# gps-power.net
KiCad netlist of a schematic drawn in EAGLE
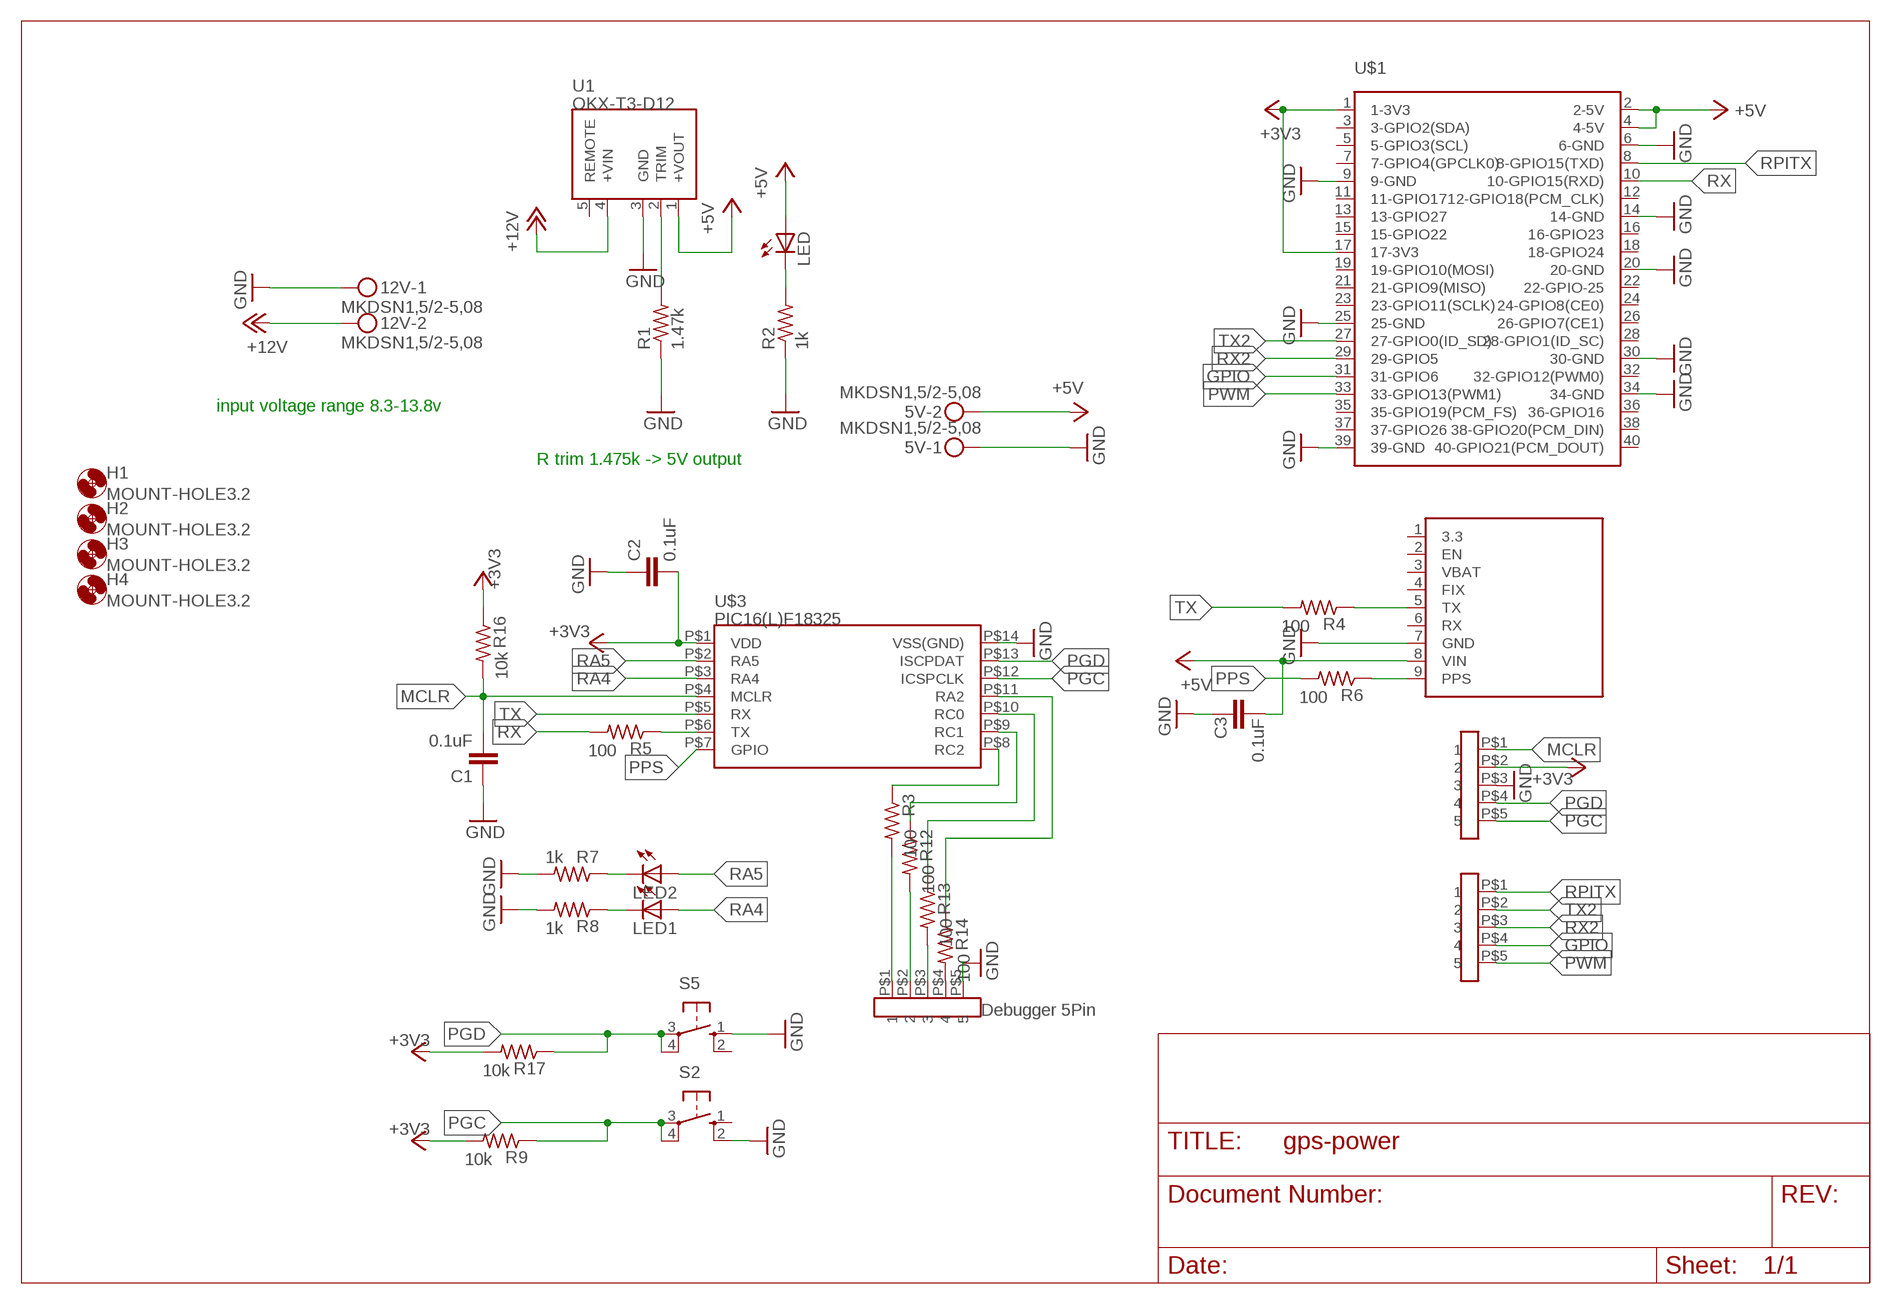
[diagram p0: schematic, sheet 1]

(export (version "E")
  (design (tool "Eeschema 10.0.6"))
  (components
    (comp (ref "5V")
      (value "MKDSN1,5/2-5,08")
      (footprint "eagle-import:MKDSN1,5_2-5,08")
      (libsource (lib "eagle-import") (part "MKDSN1,5/2-5,08"))
    )
    (comp (ref "8,9,10,11,GND")
      (value "PIN-5")
      (footprint "eagle-import:PIN-5")
      (libsource (lib "eagle-import") (part "PIN-5"))
    )
    (comp (ref "12V")
      (value "MKDSN1,5/2-5,08")
      (footprint "eagle-import:MKDSN1,5_2-5,08")
      (libsource (lib "eagle-import") (part "MKDSN1,5/2-5,08"))
    )
    (comp (ref "C1")
      (value "0.1uF")
      (footprint "eagle-import:0603")
      (libsource (lib "eagle-import") (part "0.1UF-0603-25V-5%"))
    )
    (comp (ref "C2")
      (value "0.1uF")
      (footprint "eagle-import:0603")
      (libsource (lib "eagle-import") (part "0.1UF-0603-25V-5%"))
    )
    (comp (ref "C3")
      (value "0.1uF")
      (footprint "eagle-import:0603")
      (libsource (lib "eagle-import") (part "0.1UF-0603-25V-5%"))
    )
    (comp (ref "GND")
      (value "PIN-5")
      (footprint "eagle-import:PIN-5")
      (libsource (lib "eagle-import") (part "PIN-5"))
    )
    (comp (ref "H1")
      (value "MOUNT-HOLE3.2")
      (footprint "eagle-import:3,2")
      (libsource (lib "eagle-import") (part "MOUNT-HOLE3.2"))
    )
    (comp (ref "H2")
      (value "MOUNT-HOLE3.2")
      (footprint "eagle-import:3,2")
      (libsource (lib "eagle-import") (part "MOUNT-HOLE3.2"))
    )
    (comp (ref "H3")
      (value "MOUNT-HOLE3.2")
      (footprint "eagle-import:3,2")
      (libsource (lib "eagle-import") (part "MOUNT-HOLE3.2"))
    )
    (comp (ref "H4")
      (value "MOUNT-HOLE3.2")
      (footprint "eagle-import:3,2")
      (libsource (lib "eagle-import") (part "MOUNT-HOLE3.2"))
    )
    (comp (ref "LED")
      (value "LEDCHIPLED_0603")
      (footprint "eagle-import:CHIPLED_0603")
      (libsource (lib "eagle-import") (part "LEDCHIPLED_0603"))
    )
    (comp (ref "LED1")
      (value "LEDCHIPLED_0603")
      (footprint "eagle-import:CHIPLED_0603")
      (libsource (lib "eagle-import") (part "LEDCHIPLED_0603"))
    )
    (comp (ref "LED2")
      (value "LEDCHIPLED_0603")
      (footprint "eagle-import:CHIPLED_0603")
      (libsource (lib "eagle-import") (part "LEDCHIPLED_0603"))
    )
    (comp (ref "MPLAB")
      (value "PIN-5")
      (footprint "eagle-import:PIN-5")
      (libsource (lib "eagle-import") (part "PIN-5"))
    )
    (comp (ref "R1")
      (value "1.47k")
      (footprint "eagle-import:R0603")
      (libsource (lib "eagle-import") (part "R-US_R0603"))
    )
    (comp (ref "R2")
      (value "1k")
      (footprint "eagle-import:R0603")
      (libsource (lib "eagle-import") (part "R-US_R0603"))
    )
    (comp (ref "R3")
      (value "100")
      (footprint "eagle-import:R0603")
      (libsource (lib "eagle-import") (part "R-US_R0603"))
    )
    (comp (ref "R4")
      (value "100")
      (footprint "eagle-import:R0603")
      (libsource (lib "eagle-import") (part "R-US_R0603"))
    )
    (comp (ref "R5")
      (value "100")
      (footprint "eagle-import:R0603")
      (libsource (lib "eagle-import") (part "R-US_R0603"))
    )
    (comp (ref "R6")
      (value "100")
      (footprint "eagle-import:R0603")
      (libsource (lib "eagle-import") (part "R-US_R0603"))
    )
    (comp (ref "R7")
      (value "1k")
      (footprint "eagle-import:R0603")
      (libsource (lib "eagle-import") (part "R-US_R0603"))
    )
    (comp (ref "R8")
      (value "1k")
      (footprint "eagle-import:R0603")
      (libsource (lib "eagle-import") (part "R-US_R0603"))
    )
    (comp (ref "R9")
      (value "10k")
      (footprint "eagle-import:R0603")
      (libsource (lib "eagle-import") (part "R-US_R0603"))
    )
    (comp (ref "R12")
      (value "100")
      (footprint "eagle-import:R0603")
      (libsource (lib "eagle-import") (part "R-US_R0603"))
    )
    (comp (ref "R13")
      (value "100")
      (footprint "eagle-import:R0603")
      (libsource (lib "eagle-import") (part "R-US_R0603"))
    )
    (comp (ref "R14")
      (value "100")
      (footprint "eagle-import:R0603")
      (libsource (lib "eagle-import") (part "R-US_R0603"))
    )
    (comp (ref "R16")
      (value "10k")
      (footprint "eagle-import:R0603")
      (libsource (lib "eagle-import") (part "R-US_R0603"))
    )
    (comp (ref "R17")
      (value "10k")
      (footprint "eagle-import:R0603")
      (libsource (lib "eagle-import") (part "R-US_R0603"))
    )
    (comp (ref "S2")
      (value "10-XX")
      (footprint "eagle-import:B3F-10XX")
      (fields (field (name "MPN") "B3F-1000"))
      (libsource (lib "eagle-import") (part "10-XX"))
    )
    (comp (ref "S5")
      (value "10-XX")
      (footprint "eagle-import:B3F-10XX")
      (fields (field (name "MPN") "B3F-1000"))
      (libsource (lib "eagle-import") (part "10-XX"))
    )
    (comp (ref "U$1")
      (value "GPIO-HD-2X20")
      (footprint "eagle-import:GPIO-HD-2X20")
      (libsource (lib "eagle-import") (part "GPIO-HD-2X20"))
    )
    (comp (ref "U$2")
      (value "ADA-GPS")
      (footprint "eagle-import:ADA-GPS")
      (libsource (lib "eagle-import") (part "ADA-GPS"))
    )
    (comp (ref "U$3")
      (value "PIC16(L)F18325")
      (footprint "eagle-import:DIP-S-14")
      (libsource (lib "eagle-import") (part "PIC16(L)F18325"))
    )
    (comp (ref "U1")
      (value "OKX-T3-D12")
      (footprint "eagle-import:OKX-T3-D12")
      (libsource (lib "eagle-import") (part "OKX-T3-D12"))
    )
  )
  (nets
    (net (code "1") (name "+3V3") (class "Default")
      (node (ref "C2") (pin "2") (pinfunction "2_2") (pintype "passive"))
      (node (ref "MPLAB") (pin "P$2") (pinfunction "2_P$2") (pintype "bidirectional"))
      (node (ref "R16") (pin "1") (pinfunction "1_1") (pintype "passive"))
      (node (ref "R17") (pin "2") (pinfunction "2_2") (pintype "passive"))
      (node (ref "R9") (pin "2") (pinfunction "2_2") (pintype "passive"))
      (node (ref "U$1") (pin "1") (pinfunction "1-3V3_1") (pintype "bidirectional"))
      (node (ref "U$1") (pin "17") (pinfunction "17-3V3_17") (pintype "bidirectional"))
      (node (ref "U$3") (pin "P$1") (pinfunction "VDD_P$1") (pintype "bidirectional"))
    )
    (net (code "2") (name "+5V") (class "Default")
      (node (ref "5V") (pin "2") (pinfunction "KL_2") (pintype "passive"))
      (node (ref "C3") (pin "2") (pinfunction "2_2") (pintype "passive"))
      (node (ref "LED") (pin "A") (pinfunction "A_A") (pintype "passive"))
      (node (ref "U$1") (pin "2") (pinfunction "2-5V_2") (pintype "bidirectional"))
      (node (ref "U$1") (pin "4") (pinfunction "4-5V_4") (pintype "bidirectional"))
      (node (ref "U$2") (pin "8") (pinfunction "VIN_8") (pintype "bidirectional"))
      (node (ref "U1") (pin "1") (pinfunction "+VOUT_1") (pintype "bidirectional"))
    )
    (net (code "3") (name "+12V") (class "Default")
      (node (ref "12V") (pin "2") (pinfunction "KL_2") (pintype "passive"))
      (node (ref "U1") (pin "4") (pinfunction "+VIN_4") (pintype "bidirectional"))
    )
    (net (code "4") (name "GND") (class "Default")
      (node (ref "12V") (pin "1") (pinfunction "KL_1") (pintype "passive"))
      (node (ref "5V") (pin "1") (pinfunction "KL_1") (pintype "passive"))
      (node (ref "8,9,10,11,GND") (pin "P$5") (pinfunction "5_P$5") (pintype "bidirectional"))
      (node (ref "C1") (pin "1") (pinfunction "1_1") (pintype "passive"))
      (node (ref "C2") (pin "1") (pinfunction "1_1") (pintype "passive"))
      (node (ref "C3") (pin "1") (pinfunction "1_1") (pintype "passive"))
      (node (ref "MPLAB") (pin "P$3") (pinfunction "3_P$3") (pintype "bidirectional"))
      (node (ref "R1") (pin "1") (pinfunction "1_1") (pintype "passive"))
      (node (ref "R2") (pin "1") (pinfunction "1_1") (pintype "passive"))
      (node (ref "R7") (pin "2") (pinfunction "2_2") (pintype "passive"))
      (node (ref "R8") (pin "2") (pinfunction "2_2") (pintype "passive"))
      (node (ref "S2") (pin "2") (pinfunction "S1_2") (pintype "passive"))
      (node (ref "S5") (pin "1") (pinfunction "S_1") (pintype "passive"))
      (node (ref "U$1") (pin "14") (pinfunction "14-GND_14") (pintype "bidirectional"))
      (node (ref "U$1") (pin "20") (pinfunction "20-GND_20") (pintype "bidirectional"))
      (node (ref "U$1") (pin "25") (pinfunction "25-GND_25") (pintype "bidirectional"))
      (node (ref "U$1") (pin "30") (pinfunction "30-GND_30") (pintype "bidirectional"))
      (node (ref "U$1") (pin "34") (pinfunction "34-GND_34") (pintype "bidirectional"))
      (node (ref "U$1") (pin "39") (pinfunction "39-GND_39") (pintype "bidirectional"))
      (node (ref "U$1") (pin "6") (pinfunction "6-GND_6") (pintype "bidirectional"))
      (node (ref "U$1") (pin "9") (pinfunction "9-GND_9") (pintype "bidirectional"))
      (node (ref "U$2") (pin "7") (pinfunction "GND_7") (pintype "bidirectional"))
      (node (ref "U$3") (pin "P$14") (pinfunction "VSS(GND)_P$14") (pintype "bidirectional"))
      (node (ref "U1") (pin "3") (pinfunction "GND_3") (pintype "bidirectional"))
    )
    (net (code "5") (name "GPIO") (class "Default")
      (node (ref "GND") (pin "P$4") (pinfunction "4_P$4") (pintype "bidirectional"))
      (node (ref "U$1") (pin "31") (pinfunction "31-GPIO6_31") (pintype "bidirectional"))
    )
    (net (code "6") (name "MCLR") (class "Default")
      (node (ref "C1") (pin "2") (pinfunction "2_2") (pintype "passive"))
      (node (ref "MPLAB") (pin "P$1") (pinfunction "1_P$1") (pintype "bidirectional"))
      (node (ref "R16") (pin "2") (pinfunction "2_2") (pintype "passive"))
      (node (ref "U$3") (pin "P$4") (pinfunction "MCLR_P$4") (pintype "bidirectional"))
    )
    (net (code "7") (name "Net-(8,9,10,11,GND-1)") (class "Default")
      (node (ref "8,9,10,11,GND") (pin "P$1") (pinfunction "1_P$1") (pintype "bidirectional"))
      (node (ref "R3") (pin "2") (pinfunction "2_2") (pintype "passive"))
    )
    (net (code "8") (name "Net-(8,9,10,11,GND-2)") (class "Default")
      (node (ref "8,9,10,11,GND") (pin "P$2") (pinfunction "2_P$2") (pintype "bidirectional"))
      (node (ref "R12") (pin "2") (pinfunction "2_2") (pintype "passive"))
    )
    (net (code "9") (name "Net-(8,9,10,11,GND-3)") (class "Default")
      (node (ref "8,9,10,11,GND") (pin "P$3") (pinfunction "3_P$3") (pintype "bidirectional"))
      (node (ref "R13") (pin "2") (pinfunction "2_2") (pintype "passive"))
    )
    (net (code "10") (name "Net-(8,9,10,11,GND-4)") (class "Default")
      (node (ref "8,9,10,11,GND") (pin "P$4") (pinfunction "4_P$4") (pintype "bidirectional"))
      (node (ref "R14") (pin "2") (pinfunction "2_2") (pintype "passive"))
    )
    (net (code "11") (name "Net-(LED-PadC)") (class "Default")
      (node (ref "LED") (pin "C") (pinfunction "C_C") (pintype "passive"))
      (node (ref "R2") (pin "2") (pinfunction "2_2") (pintype "passive"))
    )
    (net (code "12") (name "Net-(LED1-PadC)") (class "Default")
      (node (ref "LED1") (pin "C") (pinfunction "C_C") (pintype "passive"))
      (node (ref "R8") (pin "1") (pinfunction "1_1") (pintype "passive"))
    )
    (net (code "13") (name "Net-(LED2-PadC)") (class "Default")
      (node (ref "LED2") (pin "C") (pinfunction "C_C") (pintype "passive"))
      (node (ref "R7") (pin "1") (pinfunction "1_1") (pintype "passive"))
    )
    (net (code "14") (name "Net-(U$2-PPS)") (class "Default")
      (node (ref "R6") (pin "1") (pinfunction "1_1") (pintype "passive"))
      (node (ref "U$2") (pin "9") (pinfunction "PPS_9") (pintype "bidirectional"))
    )
    (net (code "15") (name "Net-(U$2-TX)") (class "Default")
      (node (ref "R4") (pin "1") (pinfunction "1_1") (pintype "passive"))
      (node (ref "U$2") (pin "5") (pinfunction "TX_5") (pintype "bidirectional"))
    )
    (net (code "16") (name "Net-(U$3-RA2)") (class "Default")
      (node (ref "R14") (pin "1") (pinfunction "1_1") (pintype "passive"))
      (node (ref "U$3") (pin "P$11") (pinfunction "RA2_P$11") (pintype "bidirectional"))
    )
    (net (code "17") (name "Net-(U$3-RC0)") (class "Default")
      (node (ref "R13") (pin "1") (pinfunction "1_1") (pintype "passive"))
      (node (ref "U$3") (pin "P$10") (pinfunction "RC0_P$10") (pintype "bidirectional"))
    )
    (net (code "18") (name "Net-(U$3-RC1)") (class "Default")
      (node (ref "R12") (pin "1") (pinfunction "1_1") (pintype "passive"))
      (node (ref "U$3") (pin "P$9") (pinfunction "RC1_P$9") (pintype "bidirectional"))
    )
    (net (code "19") (name "Net-(U$3-RC2)") (class "Default")
      (node (ref "R3") (pin "1") (pinfunction "1_1") (pintype "passive"))
      (node (ref "U$3") (pin "P$8") (pinfunction "RC2_P$8") (pintype "bidirectional"))
    )
    (net (code "20") (name "Net-(U$3-TX)") (class "Default")
      (node (ref "R5") (pin "1") (pinfunction "1_1") (pintype "passive"))
      (node (ref "U$3") (pin "P$6") (pinfunction "TX_P$6") (pintype "bidirectional"))
    )
    (net (code "21") (name "Net-(U1-TRIM)") (class "Default")
      (node (ref "R1") (pin "2") (pinfunction "2_2") (pintype "passive"))
      (node (ref "U1") (pin "2") (pinfunction "TRIM_2") (pintype "bidirectional"))
    )
    (net (code "22") (name "PGC") (class "Default")
      (node (ref "MPLAB") (pin "P$5") (pinfunction "5_P$5") (pintype "bidirectional"))
      (node (ref "R9") (pin "1") (pinfunction "1_1") (pintype "passive"))
      (node (ref "S2") (pin "3") (pinfunction "P_3") (pintype "passive"))
      (node (ref "S2") (pin "4") (pinfunction "P1_4") (pintype "passive"))
      (node (ref "U$3") (pin "P$12") (pinfunction "ICSPCLK_P$12") (pintype "bidirectional"))
    )
    (net (code "23") (name "PGD") (class "Default")
      (node (ref "MPLAB") (pin "P$4") (pinfunction "4_P$4") (pintype "bidirectional"))
      (node (ref "R17") (pin "1") (pinfunction "1_1") (pintype "passive"))
      (node (ref "S5") (pin "3") (pinfunction "P_3") (pintype "passive"))
      (node (ref "S5") (pin "4") (pinfunction "P1_4") (pintype "passive"))
      (node (ref "U$3") (pin "P$13") (pinfunction "ISCPDAT_P$13") (pintype "bidirectional"))
    )
    (net (code "24") (name "PPS") (class "Default")
      (node (ref "R6") (pin "2") (pinfunction "2_2") (pintype "passive"))
      (node (ref "U$3") (pin "P$7") (pinfunction "GPIO_P$7") (pintype "bidirectional"))
    )
    (net (code "25") (name "PWM") (class "Default")
      (node (ref "GND") (pin "P$5") (pinfunction "5_P$5") (pintype "bidirectional"))
      (node (ref "U$1") (pin "33") (pinfunction "33-GPIO13(PWM1)_33") (pintype "bidirectional"))
    )
    (net (code "26") (name "RA4") (class "Default")
      (node (ref "LED1") (pin "A") (pinfunction "A_A") (pintype "passive"))
      (node (ref "U$3") (pin "P$3") (pinfunction "RA4_P$3") (pintype "bidirectional"))
    )
    (net (code "27") (name "RA5") (class "Default")
      (node (ref "LED2") (pin "A") (pinfunction "A_A") (pintype "passive"))
      (node (ref "U$3") (pin "P$2") (pinfunction "RA5_P$2") (pintype "bidirectional"))
    )
    (net (code "28") (name "RPITX") (class "Default")
      (node (ref "GND") (pin "P$1") (pinfunction "1_P$1") (pintype "bidirectional"))
      (node (ref "U$1") (pin "8") (pinfunction "8-GPIO15(TXD)_8") (pintype "bidirectional"))
    )
    (net (code "29") (name "RX") (class "Default")
      (node (ref "R5") (pin "2") (pinfunction "2_2") (pintype "passive"))
      (node (ref "U$1") (pin "10") (pinfunction "10-GPIO15(RXD)_10") (pintype "bidirectional"))
    )
    (net (code "30") (name "RX2") (class "Default")
      (node (ref "GND") (pin "P$3") (pinfunction "3_P$3") (pintype "bidirectional"))
      (node (ref "U$1") (pin "29") (pinfunction "29-GPIO5_29") (pintype "bidirectional"))
    )
    (net (code "31") (name "TX") (class "Default")
      (node (ref "R4") (pin "2") (pinfunction "2_2") (pintype "passive"))
      (node (ref "U$3") (pin "P$5") (pinfunction "RX_P$5") (pintype "bidirectional"))
    )
    (net (code "32") (name "TX2") (class "Default")
      (node (ref "GND") (pin "P$2") (pinfunction "2_P$2") (pintype "bidirectional"))
      (node (ref "U$1") (pin "27") (pinfunction "27-GPIO0(ID_SD)_27") (pintype "bidirectional"))
    )
    (net (code "33") (name "unconnected-(S2-S-Pad1)") (class "Default")
      (node (ref "S2") (pin "1") (pinfunction "S_1") (pintype "passive"))
    )
    (net (code "34") (name "unconnected-(S5-S1-Pad2)") (class "Default")
      (node (ref "S5") (pin "2") (pinfunction "S1_2") (pintype "passive"))
    )
    (net (code "35") (name "unconnected-(U$1-3-GPIO2(SDA)-Pad3)") (class "Default")
      (node (ref "U$1") (pin "3") (pinfunction "3-GPIO2(SDA)_3") (pintype "bidirectional"))
    )
    (net (code "36") (name "unconnected-(U$1-5-GPIO3(SCL)-Pad5)") (class "Default")
      (node (ref "U$1") (pin "5") (pinfunction "5-GPIO3(SCL)_5") (pintype "bidirectional"))
    )
    (net (code "37") (name "unconnected-(U$1-7-GPIO4(GPCLK0)-Pad7)") (class "Default")
      (node (ref "U$1") (pin "7") (pinfunction "7-GPIO4(GPCLK0)_7") (pintype "bidirectional"))
    )
    (net (code "38") (name "unconnected-(U$1-11-GPIO17-Pad11)") (class "Default")
      (node (ref "U$1") (pin "11") (pinfunction "11-GPIO17_11") (pintype "bidirectional"))
    )
    (net (code "39") (name "unconnected-(U$1-12-GPIO18(PCM_CLK)-Pad12)") (class "Default")
      (node (ref "U$1") (pin "12") (pinfunction "12-GPIO18(PCM_CLK)_12") (pintype "bidirectional"))
    )
    (net (code "40") (name "unconnected-(U$1-13-GPIO27-Pad13)") (class "Default")
      (node (ref "U$1") (pin "13") (pinfunction "13-GPIO27_13") (pintype "bidirectional"))
    )
    (net (code "41") (name "unconnected-(U$1-15-GPIO22-Pad15)") (class "Default")
      (node (ref "U$1") (pin "15") (pinfunction "15-GPIO22_15") (pintype "bidirectional"))
    )
    (net (code "42") (name "unconnected-(U$1-16-GPIO23-Pad16)") (class "Default")
      (node (ref "U$1") (pin "16") (pinfunction "16-GPIO23_16") (pintype "bidirectional"))
    )
    (net (code "43") (name "unconnected-(U$1-18-GPIO24-Pad18)") (class "Default")
      (node (ref "U$1") (pin "18") (pinfunction "18-GPIO24_18") (pintype "bidirectional"))
    )
    (net (code "44") (name "unconnected-(U$1-19-GPIO10(MOSI)-Pad19)") (class "Default")
      (node (ref "U$1") (pin "19") (pinfunction "19-GPIO10(MOSI)_19") (pintype "bidirectional"))
    )
    (net (code "45") (name "unconnected-(U$1-21-GPIO9(MISO)-Pad21)") (class "Default")
      (node (ref "U$1") (pin "21") (pinfunction "21-GPIO9(MISO)_21") (pintype "bidirectional"))
    )
    (net (code "46") (name "unconnected-(U$1-22-GPIO-25-Pad22)") (class "Default")
      (node (ref "U$1") (pin "22") (pinfunction "22-GPIO-25_22") (pintype "bidirectional"))
    )
    (net (code "47") (name "unconnected-(U$1-23-GPIO11(SCLK)-Pad23)") (class "Default")
      (node (ref "U$1") (pin "23") (pinfunction "23-GPIO11(SCLK)_23") (pintype "bidirectional"))
    )
    (net (code "48") (name "unconnected-(U$1-24-GPIO8(CE0)-Pad24)") (class "Default")
      (node (ref "U$1") (pin "24") (pinfunction "24-GPIO8(CE0)_24") (pintype "bidirectional"))
    )
    (net (code "49") (name "unconnected-(U$1-26-GPIO7(CE1)-Pad26)") (class "Default")
      (node (ref "U$1") (pin "26") (pinfunction "26-GPIO7(CE1)_26") (pintype "bidirectional"))
    )
    (net (code "50") (name "unconnected-(U$1-28-GPIO1(ID_SC)-Pad28)") (class "Default")
      (node (ref "U$1") (pin "28") (pinfunction "28-GPIO1(ID_SC)_28") (pintype "bidirectional"))
    )
    (net (code "51") (name "unconnected-(U$1-32-GPIO12(PWM0)-Pad32)") (class "Default")
      (node (ref "U$1") (pin "32") (pinfunction "32-GPIO12(PWM0)_32") (pintype "bidirectional"))
    )
    (net (code "52") (name "unconnected-(U$1-35-GPIO19(PCM_FS)-Pad35)") (class "Default")
      (node (ref "U$1") (pin "35") (pinfunction "35-GPIO19(PCM_FS)_35") (pintype "bidirectional"))
    )
    (net (code "53") (name "unconnected-(U$1-36-GPIO16-Pad36)") (class "Default")
      (node (ref "U$1") (pin "36") (pinfunction "36-GPIO16_36") (pintype "bidirectional"))
    )
    (net (code "54") (name "unconnected-(U$1-37-GPIO26-Pad37)") (class "Default")
      (node (ref "U$1") (pin "37") (pinfunction "37-GPIO26_37") (pintype "bidirectional"))
    )
    (net (code "55") (name "unconnected-(U$1-38-GPIO20(PCM_DIN)-Pad38)") (class "Default")
      (node (ref "U$1") (pin "38") (pinfunction "38-GPIO20(PCM_DIN)_38") (pintype "bidirectional"))
    )
    (net (code "56") (name "unconnected-(U$1-40-GPIO21(PCM_DOUT)-Pad40)") (class "Default")
      (node (ref "U$1") (pin "40") (pinfunction "40-GPIO21(PCM_DOUT)_40") (pintype "bidirectional"))
    )
    (net (code "57") (name "unconnected-(U$2-3.3-Pad1)") (class "Default")
      (node (ref "U$2") (pin "1") (pinfunction "3.3_1") (pintype "bidirectional"))
    )
    (net (code "58") (name "unconnected-(U$2-EN-Pad2)") (class "Default")
      (node (ref "U$2") (pin "2") (pinfunction "EN_2") (pintype "bidirectional"))
    )
    (net (code "59") (name "unconnected-(U$2-FIX-Pad4)") (class "Default")
      (node (ref "U$2") (pin "4") (pinfunction "FIX_4") (pintype "bidirectional"))
    )
    (net (code "60") (name "unconnected-(U$2-RX-Pad6)") (class "Default")
      (node (ref "U$2") (pin "6") (pinfunction "RX_6") (pintype "bidirectional"))
    )
    (net (code "61") (name "unconnected-(U$2-VBAT-Pad3)") (class "Default")
      (node (ref "U$2") (pin "3") (pinfunction "VBAT_3") (pintype "bidirectional"))
    )
    (net (code "62") (name "unconnected-(U1-REMOTE-Pad5)") (class "Default")
      (node (ref "U1") (pin "5") (pinfunction "REMOTE_5") (pintype "bidirectional"))
    )
  )
)
